# Microcontroller.net
KiCad netlist of a schematic drawn in Altium Designer
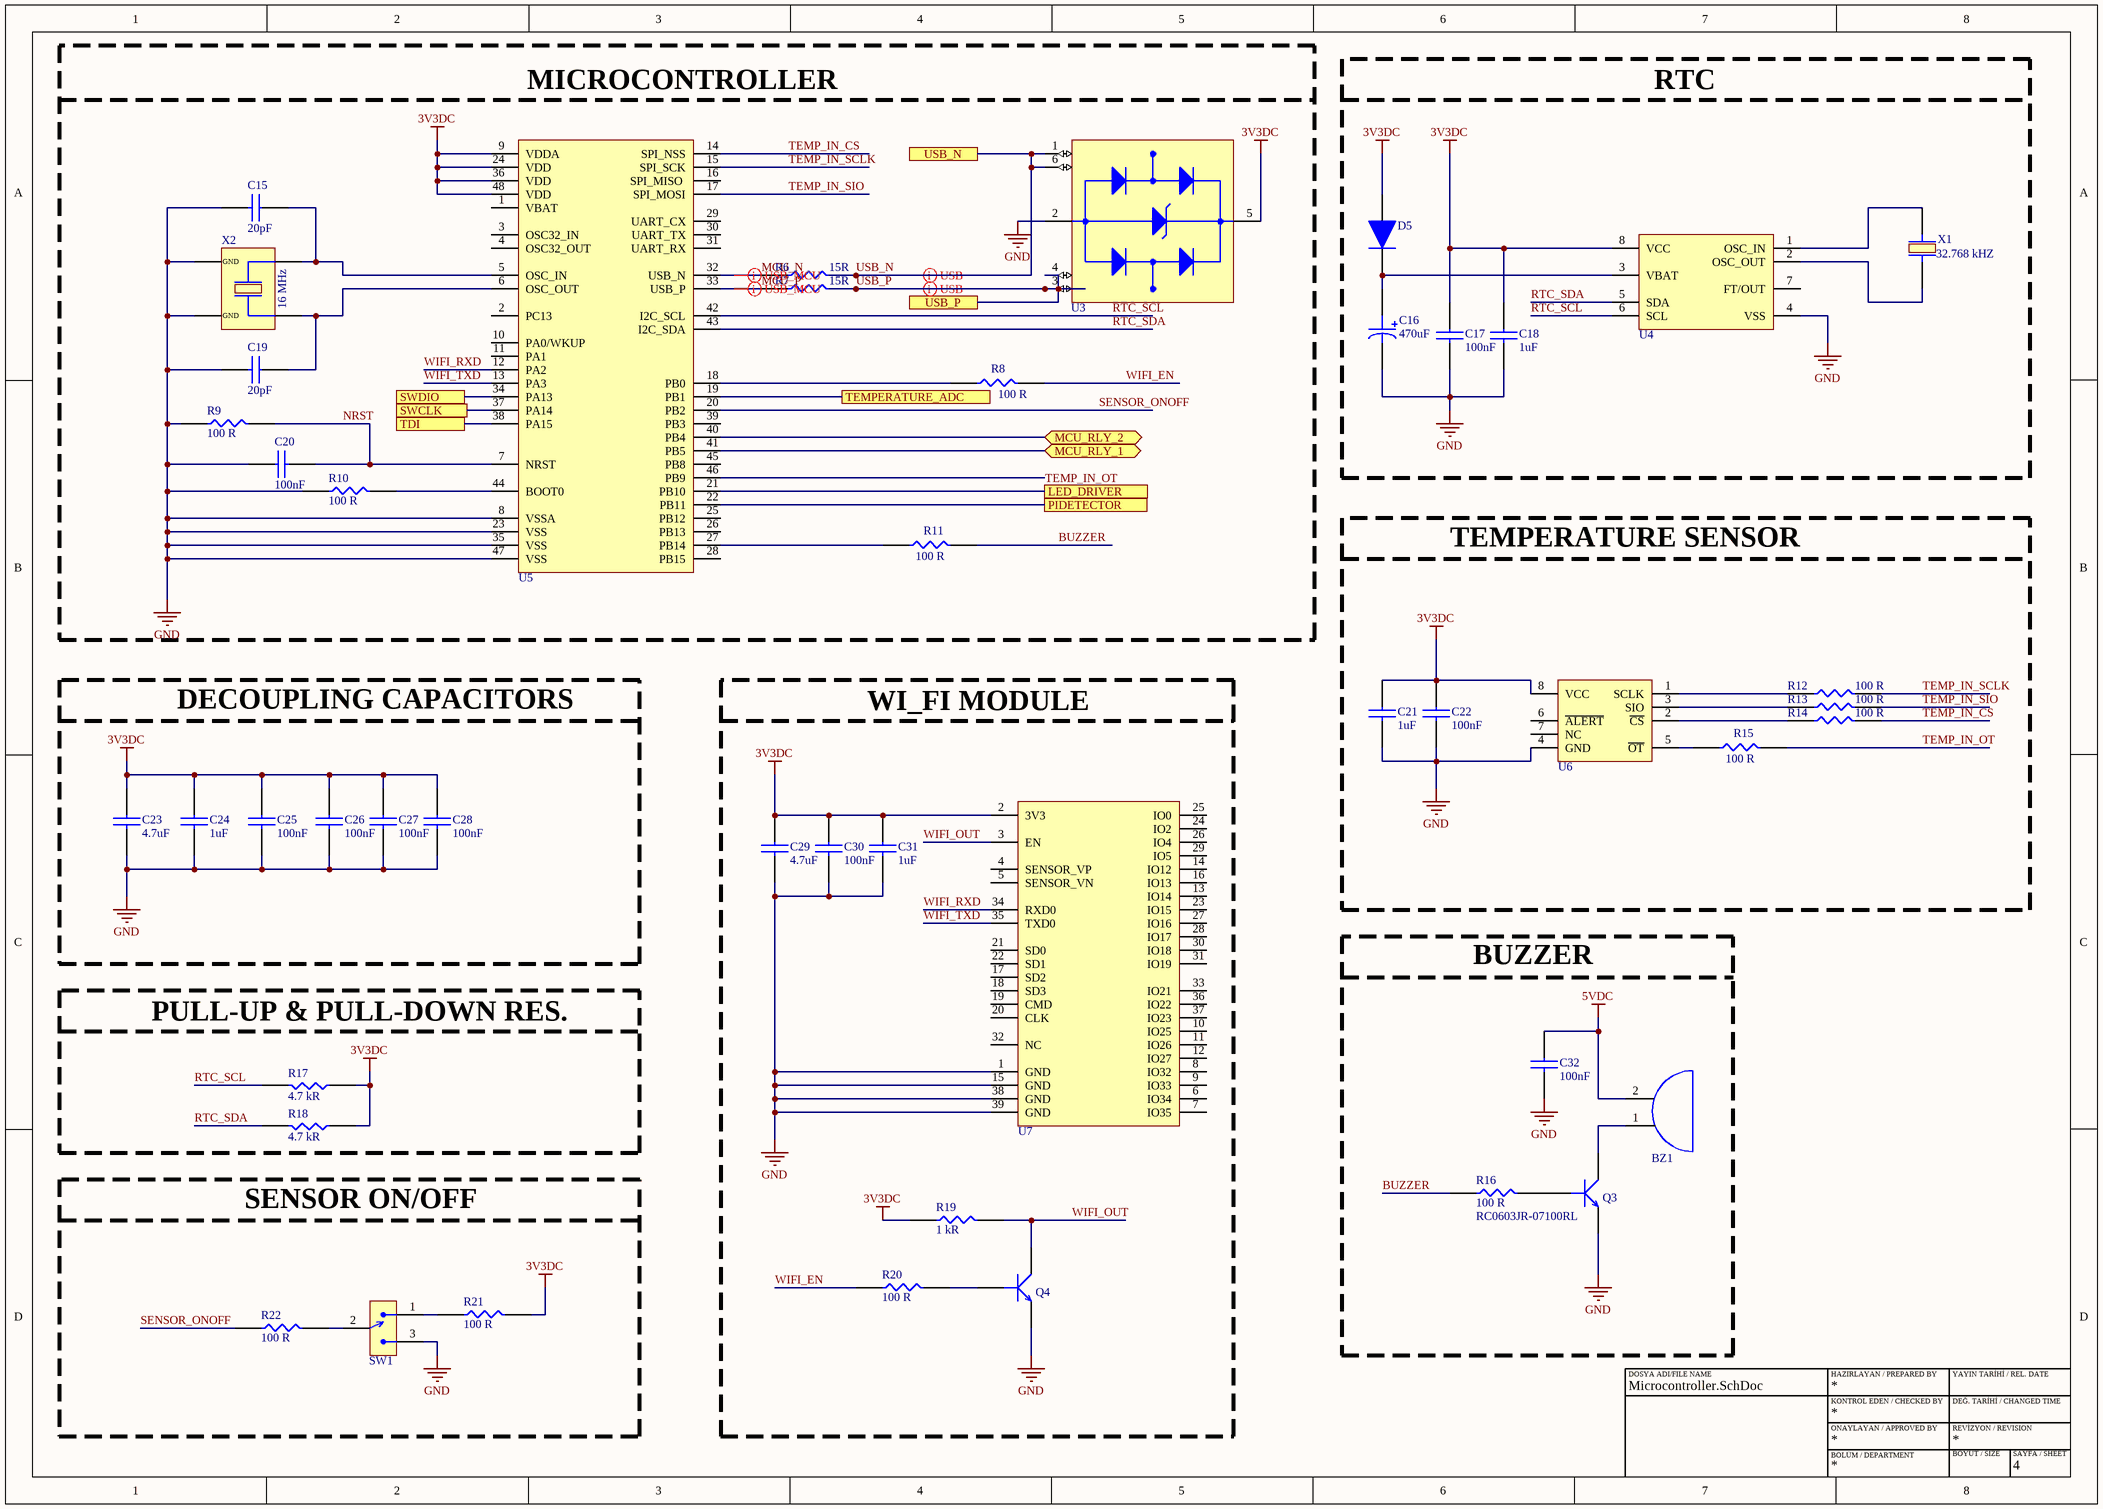
[diagram p0: Microcontroller.SchDoc]

(export (version "E")
  (design (tool "Eeschema 10.0.6"))
  (components
    (comp (ref "BZ1")
      (value "CMI-9605IC-0580T")
      (footprint "CMI-9605IC-0580T")
      (fields
        (field (name "MANUFACTURER") "Same Sky")
        (field (name "MANUFACTURER PART NUMBER") "CMI-9705-0580-SMT-TR")
      )
      (libsource (lib "Integrated_Library1") (part "CMI-9605IC-0580T"))
    )
    (comp (ref "C15")
      (value "20pF")
      (footprint "CAP_0603")
      (description "CAP CER 20pF 5% 0603")
      (fields
        (field (name "MANUFACTURER") "Samsung")
        (field (name "MANUFACTURER PART NUMBER") "CL10C200JB8NNNC")
      )
      (libsource (lib "Integrated_Library1") (part "CAP CER 20pF 0603"))
    )
    (comp (ref "C16")
      (value "470uF")
      (footprint "CAP_RADIAL_D10_P5")
      (description "CAP ALU ELEC 470uF 50V 20%")
      (fields
        (field (name "MANUFACTURER") "KEMET")
        (field (name "MANUFACTURER PART NUMBER") "ESH477M050AH4AA")
        (field (name "DESIGNED BY") "MCP")
      )
      (libsource (lib "Integrated_Library1") (part "CAP ALU ELEC 470uF 50V"))
    )
    (comp (ref "C17")
      (value "100nF")
      (footprint "CAP_0805")
      (description "CAP CER 100nF 10% 0805")
      (fields
        (field (name "MANUFACTURER") "Samsung")
        (field (name "MANUFACTURER PART NUMBER") "CL21B104KBCNNNC")
        (field (name "DESIGNED BY") "MCP")
      )
      (libsource (lib "Integrated_Library1") (part "CAP CER 100nF 0805"))
    )
    (comp (ref "C18")
      (value "1uF")
      (footprint "CAP_0805")
      (description "CAP CER 1uF 10% 0805")
      (fields
        (field (name "MANUFACTURER") "Samsung")
        (field (name "MANUFACTURER PART NUMBER") "CL21B105KBFNNNE")
        (field (name "DESIGNED BY") "MCP")
      )
      (libsource (lib "Integrated_Library1") (part "CAP CER 1uF 0805"))
    )
    (comp (ref "C19")
      (value "20pF")
      (footprint "CAP_0603")
      (description "CAP CER 20pF 5% 0603")
      (fields
        (field (name "MANUFACTURER") "Samsung")
        (field (name "MANUFACTURER PART NUMBER") "CL10C200JB8NNNC")
      )
      (libsource (lib "Integrated_Library1") (part "CAP CER 20pF 0603"))
    )
    (comp (ref "C20")
      (value "100nF")
      (footprint "CAP_0805")
      (description "CAP CER 100nF 10% 0805")
      (fields
        (field (name "MANUFACTURER") "Samsung")
        (field (name "MANUFACTURER PART NUMBER") "CL21B104KBCNNNC")
        (field (name "DESIGNED BY") "MCP")
      )
      (libsource (lib "Integrated_Library1") (part "CAP CER 100nF 0805"))
    )
    (comp (ref "C21")
      (value "1uF")
      (footprint "CAP_0805")
      (description "CAP CER 1uF 10% 0805")
      (fields
        (field (name "MANUFACTURER") "Samsung")
        (field (name "MANUFACTURER PART NUMBER") "CL21B105KBFNNNE")
        (field (name "DESIGNED BY") "MCP")
      )
      (libsource (lib "Integrated_Library1") (part "CAP CER 1uF 0805"))
    )
    (comp (ref "C22")
      (value "100nF")
      (footprint "CAP_0805")
      (description "CAP CER 100nF 10% 0805")
      (fields
        (field (name "MANUFACTURER") "Samsung")
        (field (name "MANUFACTURER PART NUMBER") "CL21B104KBCNNNC")
        (field (name "DESIGNED BY") "MCP")
      )
      (libsource (lib "Integrated_Library1") (part "CAP CER 100nF 0805"))
    )
    (comp (ref "C23")
      (value "4.7uF")
      (footprint "CAP_0805")
      (description "CAP CER 4.7uF 10% 0805")
      (fields
        (field (name "MANUFACTURER") "Samsung")
        (field (name "MANUFACTURER PART NUMBER") "CL21A475KAQNNNE")
        (field (name "DESIGNED BY") "MCP")
      )
      (libsource (lib "Integrated_Library1") (part "CAP CER 4.7uF 0805"))
    )
    (comp (ref "C24")
      (value "1uF")
      (footprint "CAP_0805")
      (description "CAP CER 1uF 10% 0805")
      (fields
        (field (name "MANUFACTURER") "Samsung")
        (field (name "MANUFACTURER PART NUMBER") "CL21B105KBFNNNE")
        (field (name "DESIGNED BY") "MCP")
      )
      (libsource (lib "Integrated_Library1") (part "CAP CER 1uF 0805"))
    )
    (comp (ref "C25")
      (value "100nF")
      (footprint "CAP_0805")
      (description "CAP CER 100nF 10% 0805")
      (fields
        (field (name "MANUFACTURER") "Samsung")
        (field (name "MANUFACTURER PART NUMBER") "CL21B104KBCNNNC")
        (field (name "DESIGNED BY") "MCP")
      )
      (libsource (lib "Integrated_Library1") (part "CAP CER 100nF 0805"))
    )
    (comp (ref "C26")
      (value "100nF")
      (footprint "CAP_0805")
      (description "CAP CER 100nF 10% 0805")
      (fields
        (field (name "MANUFACTURER") "Samsung")
        (field (name "MANUFACTURER PART NUMBER") "CL21B104KBCNNNC")
        (field (name "DESIGNED BY") "MCP")
      )
      (libsource (lib "Integrated_Library1") (part "CAP CER 100nF 0805"))
    )
    (comp (ref "C27")
      (value "100nF")
      (footprint "CAP_0805")
      (description "CAP CER 100nF 10% 0805")
      (fields
        (field (name "MANUFACTURER") "Samsung")
        (field (name "MANUFACTURER PART NUMBER") "CL21B104KBCNNNC")
        (field (name "DESIGNED BY") "MCP")
      )
      (libsource (lib "Integrated_Library1") (part "CAP CER 100nF 0805"))
    )
    (comp (ref "C28")
      (value "100nF")
      (footprint "CAP_0805")
      (description "CAP CER 100nF 10% 0805")
      (fields
        (field (name "MANUFACTURER") "Samsung")
        (field (name "MANUFACTURER PART NUMBER") "CL21B104KBCNNNC")
        (field (name "DESIGNED BY") "MCP")
      )
      (libsource (lib "Integrated_Library1") (part "CAP CER 100nF 0805"))
    )
    (comp (ref "C29")
      (value "4.7uF")
      (footprint "CAP_0805")
      (description "CAP CER 4.7uF 10% 0805")
      (fields
        (field (name "MANUFACTURER") "Samsung")
        (field (name "MANUFACTURER PART NUMBER") "CL21A475KAQNNNE")
        (field (name "DESIGNED BY") "MCP")
      )
      (libsource (lib "Integrated_Library1") (part "CAP CER 4.7uF 0805"))
    )
    (comp (ref "C30")
      (value "100nF")
      (footprint "CAP_0805")
      (description "CAP CER 100nF 10% 0805")
      (fields
        (field (name "MANUFACTURER") "Samsung")
        (field (name "MANUFACTURER PART NUMBER") "CL21B104KBCNNNC")
        (field (name "DESIGNED BY") "MCP")
      )
      (libsource (lib "Integrated_Library1") (part "CAP CER 100nF 0805"))
    )
    (comp (ref "C31")
      (value "1uF")
      (footprint "CAP_0805")
      (description "CAP CER 1uF 10% 0805")
      (fields
        (field (name "MANUFACTURER") "Samsung")
        (field (name "MANUFACTURER PART NUMBER") "CL21B105KBFNNNE")
        (field (name "DESIGNED BY") "MCP")
      )
      (libsource (lib "Integrated_Library1") (part "CAP CER 1uF 0805"))
    )
    (comp (ref "C32")
      (value "100nF")
      (footprint "CAP_0805")
      (description "CAP CER 100nF 10% 0805")
      (fields
        (field (name "MANUFACTURER") "Samsung")
        (field (name "MANUFACTURER PART NUMBER") "CL21B104KBCNNNC")
        (field (name "DESIGNED BY") "MCP")
      )
      (libsource (lib "Integrated_Library1") (part "CAP CER 100nF 0805"))
    )
    (comp (ref "D5")
      (value "1N4148WS")
      (footprint "SOD323F")
      (description "Diode,150mA, 75V V")
      (fields (field (name "MANUFACTURER") "onsemi") (field (name "DESIGNED BY") "MCP"))
      (libsource (lib "Integrated_Library1") (part "1N4148WS"))
    )
    (comp (ref "Q3")
      (value "MMBT3904.7.F")
      (footprint "SOT-23F")
      (description "Small Signal Bipolar Transistor, 0.2A I(C), 40V V(BR)CEO, 1-Element, NPN, Silicon")
      (fields
        (field (name "MANUFACTURER") "Diodes Zetex")
        (field (name "MANUFACTURER PART NUMBER") "MMBT3904-7-F")
        (field (name "DESIGNED BY") "MCP")
      )
      (libsource (lib "Integrated_Library1") (part "MMBT3904.7.F"))
    )
    (comp (ref "Q4")
      (value "MMBT3904.7.F")
      (footprint "SOT-23F")
      (description "Small Signal Bipolar Transistor, 0.2A I(C), 40V V(BR)CEO, 1-Element, NPN, Silicon")
      (fields
        (field (name "MANUFACTURER") "Diodes Zetex")
        (field (name "MANUFACTURER PART NUMBER") "MMBT3904-7-F")
        (field (name "DESIGNED BY") "MCP")
      )
      (libsource (lib "Integrated_Library1") (part "MMBT3904.7.F"))
    )
    (comp (ref "R6")
      (value "15R")
      (footprint "RES_0603")
      (fields
        (field (name "MANUFACTURER") "Yageo")
        (field (name "MANUFACTURER PART NUMBER") "RC0603JR-0715RL")
        (field (name "TOLERANCE") "5%")
      )
      (libsource (lib "Integrated_Library1") (part "RES 15 OHM 0603"))
    )
    (comp (ref "R7")
      (value "15R")
      (footprint "RES_0603")
      (fields
        (field (name "MANUFACTURER") "Yageo")
        (field (name "MANUFACTURER PART NUMBER") "RC0603JR-0715RL")
        (field (name "TOLERANCE") "5%")
      )
      (libsource (lib "Integrated_Library1") (part "RES 15 OHM 0603"))
    )
    (comp (ref "R8")
      (value "100 R")
      (footprint "RES_0603")
      (fields
        (field (name "MANUFACTURER") "Yageo")
        (field (name "MANUFACTURER PART NUMBER") "RC0603JR-07100RL")
        (field (name "TOLERANCE") "5%")
      )
      (libsource (lib "Integrated_Library1") (part "RES 100 OHM 0603"))
    )
    (comp (ref "R9")
      (value "100 R")
      (footprint "RES_0603")
      (fields
        (field (name "MANUFACTURER") "Yageo")
        (field (name "MANUFACTURER PART NUMBER") "RC0603JR-07100RL")
        (field (name "TOLERANCE") "5%")
      )
      (libsource (lib "Integrated_Library1") (part "RES 100 OHM 0603"))
    )
    (comp (ref "R10")
      (value "100 R")
      (footprint "RES_0603")
      (fields
        (field (name "MANUFACTURER") "Yageo")
        (field (name "MANUFACTURER PART NUMBER") "RC0603JR-07100RL")
        (field (name "TOLERANCE") "5%")
      )
      (libsource (lib "Integrated_Library1") (part "RES 100 OHM 0603"))
    )
    (comp (ref "R11")
      (value "100 R")
      (footprint "RES_0603")
      (fields
        (field (name "MANUFACTURER") "Yageo")
        (field (name "MANUFACTURER PART NUMBER") "RC0603JR-07100RL")
        (field (name "TOLERANCE") "5%")
      )
      (libsource (lib "Integrated_Library1") (part "RES 100 OHM 0603"))
    )
    (comp (ref "R12")
      (value "100 R")
      (footprint "RES_0603")
      (fields
        (field (name "MANUFACTURER") "Yageo")
        (field (name "MANUFACTURER PART NUMBER") "RC0603JR-07100RL")
        (field (name "TOLERANCE") "5%")
      )
      (libsource (lib "Integrated_Library1") (part "RES 100 OHM 0603"))
    )
    (comp (ref "R13")
      (value "100 R")
      (footprint "RES_0603")
      (fields
        (field (name "MANUFACTURER") "Yageo")
        (field (name "MANUFACTURER PART NUMBER") "RC0603JR-07100RL")
        (field (name "TOLERANCE") "5%")
      )
      (libsource (lib "Integrated_Library1") (part "RES 100 OHM 0603"))
    )
    (comp (ref "R14")
      (value "100 R")
      (footprint "RES_0603")
      (fields
        (field (name "MANUFACTURER") "Yageo")
        (field (name "MANUFACTURER PART NUMBER") "RC0603JR-07100RL")
        (field (name "TOLERANCE") "5%")
      )
      (libsource (lib "Integrated_Library1") (part "RES 100 OHM 0603"))
    )
    (comp (ref "R15")
      (value "100 R")
      (footprint "RES_0603")
      (fields
        (field (name "MANUFACTURER") "Yageo")
        (field (name "MANUFACTURER PART NUMBER") "RC0603JR-07100RL")
        (field (name "TOLERANCE") "5%")
      )
      (libsource (lib "Integrated_Library1") (part "RES 100 OHM 0603"))
    )
    (comp (ref "R16")
      (value "RC0603JR-07100RL")
      (footprint "RES_0603")
      (fields
        (field (name "MANUFACTURER") "Yageo")
        (field (name "TOLERANCE") "5%")
        (field (name "POWER") "100mW")
        (field (name "ALTIUM_VALUE") "100 R")
      )
      (libsource (lib "Integrated_Library1") (part "RES 100 OHM 0603"))
    )
    (comp (ref "R17")
      (value "4.7 kR")
      (footprint "RES_0603")
      (fields
        (field (name "MANUFACTURER") "Yageo")
        (field (name "MANUFACTURER PART NUMBER") "RC0603JR-074K7L")
        (field (name "TOLERANCE") "5%")
      )
      (libsource (lib "Integrated_Library1") (part "RES 4K7 OHM 0603"))
    )
    (comp (ref "R18")
      (value "4.7 kR")
      (footprint "RES_0603")
      (fields
        (field (name "MANUFACTURER") "Yageo")
        (field (name "MANUFACTURER PART NUMBER") "RC0603JR-074K7L")
        (field (name "TOLERANCE") "5%")
      )
      (libsource (lib "Integrated_Library1") (part "RES 4K7 OHM 0603"))
    )
    (comp (ref "R19")
      (value "1 kR")
      (footprint "RES_0603")
      (fields
        (field (name "MANUFACTURER") "Stackpole Electronics")
        (field (name "MANUFACTURER PART NUMBER") "RMCF0603FT1K00")
        (field (name "TOLERANCE") "1%")
      )
      (libsource (lib "Integrated_Library1") (part "RES 1K OHM 0603"))
    )
    (comp (ref "R20")
      (value "100 R")
      (footprint "RES_0603")
      (fields
        (field (name "MANUFACTURER") "Yageo")
        (field (name "MANUFACTURER PART NUMBER") "RC0603JR-07100RL")
        (field (name "TOLERANCE") "5%")
      )
      (libsource (lib "Integrated_Library1") (part "RES 100 OHM 0603"))
    )
    (comp (ref "R21")
      (value "100 R")
      (footprint "RES_0603")
      (fields
        (field (name "MANUFACTURER") "Yageo")
        (field (name "MANUFACTURER PART NUMBER") "RC0603JR-07100RL")
        (field (name "TOLERANCE") "5%")
      )
      (libsource (lib "Integrated_Library1") (part "RES 100 OHM 0603"))
    )
    (comp (ref "R22")
      (value "100 R")
      (footprint "RES_0603")
      (fields
        (field (name "MANUFACTURER") "Yageo")
        (field (name "MANUFACTURER PART NUMBER") "RC0603JR-07100RL")
        (field (name "TOLERANCE") "5%")
      )
      (libsource (lib "Integrated_Library1") (part "RES 100 OHM 0603"))
    )
    (comp (ref "SW1")
      (value "EG1215AA")
      (footprint "EG1215AA")
      (description "Slide Switch")
      (fields (field (name "MANUFACTURER") "E-Switch"))
      (libsource (lib "Integrated_Library1") (part "EG1215AA"))
    )
    (comp (ref "U3")
      (value "USBLC6-2SC6")
      (footprint "SOT23-6L")
      (description "Trans Voltage Suppressor Diode, 5V V(RWM), Unidirectional, 1 Element, Silicon")
      (fields (field (name "MANUFACTURER") "STMicroelectronics"))
      (libsource (lib "Integrated_Library1") (part "USB PROTECTION"))
    )
    (comp (ref "U4")
      (value "M41T00M6F")
      (footprint "SOIC-8")
      (description "Real Time Clock, Volatile, CMOS, PDSO8")
      (fields (field (name "MANUFACTURER") "STMicroelectronics") (field (name "DESIGNED BY") "MCP"))
      (libsource (lib "Integrated_Library1") (part "M41T00M6F"))
    )
    (comp (ref "U5")
      (value "STM32F103C6T6A")
      (footprint "LQFP-48")
      (description "MCU 32-bit STM32F ARM Cortex M3 RISC 32KB Flash 2.5V/3.3V 48-Pin LQFP Tray")
      (fields (field (name "MANUFACTURER") "STMicroelectronics") (field (name "DESIGNED BY") "MCP"))
      (libsource (lib "Integrated_Library1") (part "STM32F103C6T6A"))
    )
    (comp (ref "U6")
      (value "MAX6662MSA+")
      (footprint "SOIC-8")
      (description "Serial Switch/Digital Sensor, 12 Bit(s), 2.50Cel, BICMOS, Rectangular, 8 Pin, Surface Mount")
      (fields (field (name "MANUFACTURER") "Maxim") (field (name "DESIGNED BY") "MCP"))
      (libsource (lib "Integrated_Library1") (part "MAX6662MSA+"))
    )
    (comp (ref "U7")
      (value "ESP32-WROOM-32E")
      (footprint "ESP32-32E")
      (description "ESP32-WROOM-32E 4MB Flash")
      (fields
        (field (name "MANUFACTURER") "Espressif Systems")
        (field (name "MANUFACTURER PART NUMBER") "ESP32-DEVKITC-32E")
        (field (name "DESIGNED BY") "MCP")
      )
      (libsource (lib "Integrated_Library1") (part "ESP32-WROOM-32E"))
    )
    (comp (ref "X1")
      (value "ABS05-32.768KHZ-T")
      (footprint "ABS05")
      (description "Parallel - Fundamental Quartz Crystal, 0.032768MHz Nom")
      (fields (field (name "MANUFACTURER") "Abracon") (field (name "OPERATING FREQUENCY-NOM") "32.768 kHZ"))
      (libsource (lib "Integrated_Library1") (part "CRYSTAL 32768kHZ"))
    )
    (comp (ref "X2")
      (value "ECS-160-20-30B-TR")
      (footprint "ECS")
      (description "Parallel - Fundamental Quartz Crystal, 16MHz Nom")
      (fields
        (field (name "MANUFACTURER") "ECS International")
        (field (name "OPERATING FREQUENCY-NOM") "16 MHz")
      )
      (libsource (lib "Integrated_Library1") (part "CRYSTAL 16MHz"))
    )
  )
  (nets
    (net (code "1") (name "/BUZZER") (class "Default")
      (node (ref "R11") (pin "2") (pinfunction "2_2") (pintype "passive"))
      (node (ref "R16") (pin "1") (pinfunction "1_1") (pintype "passive"))
    )
    (net (code "2") (name "/LED_DRIVER") (class "Default")
      (node (ref "U5") (pin "21") (pinfunction "PB10_21") (pintype "passive"))
    )
    (net (code "3") (name "/MCU_N") (class "Default")
      (node (ref "R6") (pin "1") (pinfunction "1_1") (pintype "passive"))
      (node (ref "U5") (pin "32") (pinfunction "USB_N_32") (pintype "passive"))
    )
    (net (code "4") (name "/MCU_P") (class "Default")
      (node (ref "R7") (pin "1") (pinfunction "1_1") (pintype "passive"))
      (node (ref "U5") (pin "33") (pinfunction "USB_P_33") (pintype "passive"))
    )
    (net (code "5") (name "/MCU_RLY_1") (class "Default")
      (node (ref "U5") (pin "41") (pinfunction "PB5_41") (pintype "passive"))
    )
    (net (code "6") (name "/MCU_RLY_2") (class "Default")
      (node (ref "U5") (pin "40") (pinfunction "PB4_40") (pintype "passive"))
    )
    (net (code "7") (name "/NRST") (class "Default")
      (node (ref "C20") (pin "1") (pinfunction "1_1") (pintype "passive"))
      (node (ref "R9") (pin "2") (pinfunction "2_2") (pintype "passive"))
      (node (ref "U5") (pin "7") (pinfunction "NRST_7") (pintype "passive"))
    )
    (net (code "8") (name "/PIDETECTOR") (class "Default")
      (node (ref "U5") (pin "22") (pinfunction "PB11_22") (pintype "passive"))
    )
    (net (code "9") (name "/RTC_SCL") (class "Default")
      (node (ref "R17") (pin "1") (pinfunction "1_1") (pintype "passive"))
      (node (ref "U4") (pin "6") (pinfunction "SCL_6") (pintype "passive"))
      (node (ref "U5") (pin "42") (pinfunction "I2C_SCL_42") (pintype "passive"))
    )
    (net (code "10") (name "/RTC_SDA") (class "Default")
      (node (ref "R18") (pin "1") (pinfunction "1_1") (pintype "passive"))
      (node (ref "U4") (pin "5") (pinfunction "SDA_5") (pintype "passive"))
      (node (ref "U5") (pin "43") (pinfunction "I2C_SDA_43") (pintype "passive"))
    )
    (net (code "11") (name "/SENSOR_ONOFF") (class "Default")
      (node (ref "R22") (pin "1") (pinfunction "1_1") (pintype "passive"))
      (node (ref "U5") (pin "20") (pinfunction "PB2_20") (pintype "passive"))
    )
    (net (code "12") (name "/SWCLK") (class "Default")
      (node (ref "U5") (pin "37") (pinfunction "PA14_37") (pintype "passive"))
    )
    (net (code "13") (name "/SWDIO") (class "Default")
      (node (ref "U5") (pin "34") (pinfunction "PA13_34") (pintype "passive"))
    )
    (net (code "14") (name "/TDI") (class "Default")
      (node (ref "U5") (pin "38") (pinfunction "PA15_38") (pintype "passive"))
    )
    (net (code "15") (name "/TEMPERATURE_ADC") (class "Default")
      (node (ref "U5") (pin "19") (pinfunction "PB1_19") (pintype "passive"))
    )
    (net (code "16") (name "/TEMP_IN_CS") (class "Default")
      (node (ref "R14") (pin "2") (pinfunction "2_2") (pintype "passive"))
      (node (ref "U5") (pin "14") (pinfunction "SPI_NSS_14") (pintype "passive"))
    )
    (net (code "17") (name "/TEMP_IN_OT") (class "Default")
      (node (ref "R15") (pin "2") (pinfunction "2_2") (pintype "passive"))
      (node (ref "U5") (pin "46") (pinfunction "PB9_46") (pintype "passive"))
    )
    (net (code "18") (name "/TEMP_IN_SCLK") (class "Default")
      (node (ref "R12") (pin "2") (pinfunction "2_2") (pintype "passive"))
      (node (ref "U5") (pin "15") (pinfunction "SPI_SCK_15") (pintype "passive"))
    )
    (net (code "19") (name "/TEMP_IN_SIO") (class "Default")
      (node (ref "R13") (pin "2") (pinfunction "2_2") (pintype "passive"))
      (node (ref "U5") (pin "17") (pinfunction "SPI_MOSI_17") (pintype "passive"))
    )
    (net (code "20") (name "/USB_N") (class "Default")
      (node (ref "R6") (pin "2") (pinfunction "2_2") (pintype "passive"))
      (node (ref "U3") (pin "1") (pinfunction "I/O1_IN_1") (pintype "bidirectional"))
      (node (ref "U3") (pin "6") (pinfunction "I/O1_OUT_6") (pintype "bidirectional"))
    )
    (net (code "21") (name "/USB_P") (class "Default")
      (node (ref "R7") (pin "2") (pinfunction "2_2") (pintype "passive"))
      (node (ref "U3") (pin "3") (pinfunction "I/O2_IN_3") (pintype "bidirectional"))
      (node (ref "U3") (pin "4") (pinfunction "I/O2_OUT_4") (pintype "bidirectional"))
    )
    (net (code "22") (name "/WIFI_EN") (class "Default")
      (node (ref "R20") (pin "1") (pinfunction "1_1") (pintype "passive"))
      (node (ref "R8") (pin "2") (pinfunction "2_2") (pintype "passive"))
    )
    (net (code "23") (name "/WIFI_OUT") (class "Default")
      (node (ref "Q4") (pin "3") (pinfunction "C_3") (pintype "passive"))
      (node (ref "R19") (pin "2") (pinfunction "2_2") (pintype "passive"))
      (node (ref "U7") (pin "3") (pinfunction "EN_3") (pintype "passive"))
    )
    (net (code "24") (name "/WIFI_RXD") (class "Default")
      (node (ref "U5") (pin "12") (pinfunction "PA2_12") (pintype "passive"))
      (node (ref "U7") (pin "34") (pinfunction "RXD0_34") (pintype "passive"))
    )
    (net (code "25") (name "/WIFI_TXD") (class "Default")
      (node (ref "U5") (pin "13") (pinfunction "PA3_13") (pintype "passive"))
      (node (ref "U7") (pin "35") (pinfunction "TXD0_35") (pintype "passive"))
    )
    (net (code "26") (name "3V3DC") (class "Default")
      (node (ref "C17") (pin "2") (pinfunction "2_2") (pintype "passive"))
      (node (ref "C18") (pin "2") (pinfunction "2_2") (pintype "passive"))
      (node (ref "C21") (pin "2") (pinfunction "2_2") (pintype "passive"))
      (node (ref "C22") (pin "2") (pinfunction "2_2") (pintype "passive"))
      (node (ref "C23") (pin "2") (pinfunction "2_2") (pintype "passive"))
      (node (ref "C24") (pin "2") (pinfunction "2_2") (pintype "passive"))
      (node (ref "C25") (pin "2") (pinfunction "2_2") (pintype "passive"))
      (node (ref "C26") (pin "2") (pinfunction "2_2") (pintype "passive"))
      (node (ref "C27") (pin "2") (pinfunction "2_2") (pintype "passive"))
      (node (ref "C28") (pin "2") (pinfunction "2_2") (pintype "passive"))
      (node (ref "C29") (pin "2") (pinfunction "2_2") (pintype "passive"))
      (node (ref "C30") (pin "2") (pinfunction "2_2") (pintype "passive"))
      (node (ref "C31") (pin "2") (pinfunction "2_2") (pintype "passive"))
      (node (ref "D5") (pin "2") (pinfunction "2_2") (pintype "passive"))
      (node (ref "R17") (pin "2") (pinfunction "2_2") (pintype "passive"))
      (node (ref "R18") (pin "2") (pinfunction "2_2") (pintype "passive"))
      (node (ref "R19") (pin "1") (pinfunction "1_1") (pintype "passive"))
      (node (ref "R21") (pin "2") (pinfunction "2_2") (pintype "passive"))
      (node (ref "U3") (pin "5") (pinfunction "VBUS_5") (pintype "power_in"))
      (node (ref "U4") (pin "8") (pinfunction "VCC_8") (pintype "passive"))
      (node (ref "U5") (pin "24") (pinfunction "VDD_24") (pintype "passive"))
      (node (ref "U5") (pin "36") (pinfunction "VDD_36") (pintype "passive"))
      (node (ref "U5") (pin "48") (pinfunction "VDD_48") (pintype "passive"))
      (node (ref "U5") (pin "9") (pinfunction "VDDA_9") (pintype "passive"))
      (node (ref "U6") (pin "8") (pinfunction "VCC_8") (pintype "passive"))
      (node (ref "U7") (pin "2") (pinfunction "3V3_2") (pintype "passive"))
    )
    (net (code "27") (name "5VDC") (class "Default")
      (node (ref "BZ1") (pin "2") (pinfunction "2_2") (pintype "passive"))
      (node (ref "C32") (pin "2") (pinfunction "2_2") (pintype "passive"))
    )
    (net (code "28") (name "GND") (class "Default")
      (node (ref "C15") (pin "1") (pinfunction "1_1") (pintype "passive"))
      (node (ref "C16") (pin "2") (pinfunction "2_2") (pintype "passive"))
      (node (ref "C17") (pin "1") (pinfunction "1_1") (pintype "passive"))
      (node (ref "C18") (pin "1") (pinfunction "1_1") (pintype "passive"))
      (node (ref "C19") (pin "1") (pinfunction "1_1") (pintype "passive"))
      (node (ref "C20") (pin "2") (pinfunction "2_2") (pintype "passive"))
      (node (ref "C21") (pin "1") (pinfunction "1_1") (pintype "passive"))
      (node (ref "C22") (pin "1") (pinfunction "1_1") (pintype "passive"))
      (node (ref "C23") (pin "1") (pinfunction "1_1") (pintype "passive"))
      (node (ref "C24") (pin "1") (pinfunction "1_1") (pintype "passive"))
      (node (ref "C25") (pin "1") (pinfunction "1_1") (pintype "passive"))
      (node (ref "C26") (pin "1") (pinfunction "1_1") (pintype "passive"))
      (node (ref "C27") (pin "1") (pinfunction "1_1") (pintype "passive"))
      (node (ref "C28") (pin "1") (pinfunction "1_1") (pintype "passive"))
      (node (ref "C29") (pin "1") (pinfunction "1_1") (pintype "passive"))
      (node (ref "C30") (pin "1") (pinfunction "1_1") (pintype "passive"))
      (node (ref "C31") (pin "1") (pinfunction "1_1") (pintype "passive"))
      (node (ref "C32") (pin "1") (pinfunction "1_1") (pintype "passive"))
      (node (ref "Q3") (pin "2") (pinfunction "E_2") (pintype "passive"))
      (node (ref "Q4") (pin "2") (pinfunction "E_2") (pintype "passive"))
      (node (ref "R10") (pin "1") (pinfunction "1_1") (pintype "passive"))
      (node (ref "R9") (pin "1") (pinfunction "1_1") (pintype "passive"))
      (node (ref "SW1") (pin "3") (pinfunction "3_3") (pintype "passive"))
      (node (ref "U3") (pin "2") (pinfunction "GND_2") (pintype "power_in"))
      (node (ref "U4") (pin "4") (pinfunction "VSS_4") (pintype "passive"))
      (node (ref "U5") (pin "23") (pinfunction "VSS_23") (pintype "passive"))
      (node (ref "U5") (pin "35") (pinfunction "VSS_35") (pintype "passive"))
      (node (ref "U5") (pin "47") (pinfunction "VSS_47") (pintype "passive"))
      (node (ref "U5") (pin "8") (pinfunction "VSSA_8") (pintype "passive"))
      (node (ref "U6") (pin "4") (pinfunction "GND_4") (pintype "passive"))
      (node (ref "U7") (pin "1") (pinfunction "GND_1") (pintype "passive"))
      (node (ref "U7") (pin "15") (pinfunction "GND_15") (pintype "passive"))
      (node (ref "U7") (pin "38") (pinfunction "GND_38") (pintype "passive"))
      (node (ref "U7") (pin "39") (pinfunction "GND_39") (pintype "passive"))
      (node (ref "X2") (pin "2") (pinfunction "GND_2") (pintype "passive"))
      (node (ref "X2") (pin "4") (pinfunction "GND_4") (pintype "passive"))
    )
    (net (code "29") (name "Net-(Q3-B)") (class "Default")
      (node (ref "Q3") (pin "1") (pinfunction "B_1") (pintype "passive"))
      (node (ref "R16") (pin "2") (pinfunction "2_2") (pintype "passive"))
    )
    (net (code "30") (name "Net-(Q3-C)") (class "Default")
      (node (ref "BZ1") (pin "1") (pinfunction "1_1") (pintype "passive"))
      (node (ref "Q3") (pin "3") (pinfunction "C_3") (pintype "passive"))
    )
    (net (code "31") (name "Net-(Q4-B)") (class "Default")
      (node (ref "Q4") (pin "1") (pinfunction "B_1") (pintype "passive"))
      (node (ref "R20") (pin "2") (pinfunction "2_2") (pintype "passive"))
    )
    (net (code "32") (name "Net-(R21-Pad1)") (class "Default")
      (node (ref "R21") (pin "1") (pinfunction "1_1") (pintype "passive"))
      (node (ref "SW1") (pin "1") (pinfunction "1_1") (pintype "passive"))
    )
    (net (code "33") (name "Net-(R22-Pad2)") (class "Default")
      (node (ref "R22") (pin "2") (pinfunction "2_2") (pintype "passive"))
      (node (ref "SW1") (pin "2") (pinfunction "2_2") (pintype "passive"))
    )
    (net (code "34") (name "Net-(U4-OSC_IN)") (class "Default")
      (node (ref "U4") (pin "1") (pinfunction "OSC_IN_1") (pintype "passive"))
      (node (ref "X1") (pin "2") (pinfunction "2_2") (pintype "passive"))
    )
    (net (code "35") (name "Net-(U4-OSC_OUT)") (class "Default")
      (node (ref "U4") (pin "2") (pinfunction "OSC_OUT_2") (pintype "passive"))
      (node (ref "X1") (pin "1") (pinfunction "1_1") (pintype "passive"))
    )
    (net (code "36") (name "Net-(U4-VBAT)") (class "Default")
      (node (ref "C16") (pin "1") (pinfunction "1_1") (pintype "passive"))
      (node (ref "D5") (pin "1") (pinfunction "1_1") (pintype "passive"))
      (node (ref "U4") (pin "3") (pinfunction "VBAT_3") (pintype "passive"))
    )
    (net (code "37") (name "Net-(U5-BOOT0)") (class "Default")
      (node (ref "R10") (pin "2") (pinfunction "2_2") (pintype "passive"))
      (node (ref "U5") (pin "44") (pinfunction "BOOT0_44") (pintype "passive"))
    )
    (net (code "38") (name "Net-(U5-OSC_IN)") (class "Default")
      (node (ref "C15") (pin "2") (pinfunction "2_2") (pintype "passive"))
      (node (ref "U5") (pin "5") (pinfunction "OSC_IN_5") (pintype "passive"))
      (node (ref "X2") (pin "3") (pinfunction "3_3") (pintype "passive"))
    )
    (net (code "39") (name "Net-(U5-OSC_OUT)") (class "Default")
      (node (ref "C19") (pin "2") (pinfunction "2_2") (pintype "passive"))
      (node (ref "U5") (pin "6") (pinfunction "OSC_OUT_6") (pintype "passive"))
      (node (ref "X2") (pin "1") (pinfunction "1_1") (pintype "passive"))
    )
    (net (code "40") (name "Net-(U5-PB0)") (class "Default")
      (node (ref "R8") (pin "1") (pinfunction "1_1") (pintype "passive"))
      (node (ref "U5") (pin "18") (pinfunction "PB0_18") (pintype "passive"))
    )
    (net (code "41") (name "Net-(U5-PB14)") (class "Default")
      (node (ref "R11") (pin "1") (pinfunction "1_1") (pintype "passive"))
      (node (ref "U5") (pin "27") (pinfunction "PB14_27") (pintype "passive"))
    )
    (net (code "42") (name "Net-(U6-SCLK)") (class "Default")
      (node (ref "R12") (pin "1") (pinfunction "1_1") (pintype "passive"))
      (node (ref "U6") (pin "1") (pinfunction "SCLK_1") (pintype "passive"))
    )
    (net (code "43") (name "Net-(U6-SIO)") (class "Default")
      (node (ref "R13") (pin "1") (pinfunction "1_1") (pintype "passive"))
      (node (ref "U6") (pin "3") (pinfunction "SIO_3") (pintype "passive"))
    )
    (net (code "44") (name "Net-(U6-~{CS})") (class "Default")
      (node (ref "R14") (pin "1") (pinfunction "1_1") (pintype "passive"))
      (node (ref "U6") (pin "2") (pinfunction "~{CS}_2") (pintype "passive"))
    )
    (net (code "45") (name "Net-(U6-~{OT})") (class "Default")
      (node (ref "R15") (pin "1") (pinfunction "1_1") (pintype "passive"))
      (node (ref "U6") (pin "5") (pinfunction "~{OT}_5") (pintype "passive"))
    )
    (net (code "46") (name "unconnected-(U4-FT{slash}OUT-Pad7)") (class "Default")
      (node (ref "U4") (pin "7") (pinfunction "FT/OUT_7") (pintype "passive"))
    )
    (net (code "47") (name "unconnected-(U5-OSC32_IN-Pad3)") (class "Default")
      (node (ref "U5") (pin "3") (pinfunction "OSC32_IN_3") (pintype "passive"))
    )
    (net (code "48") (name "unconnected-(U5-OSC32_OUT-Pad4)") (class "Default")
      (node (ref "U5") (pin "4") (pinfunction "OSC32_OUT_4") (pintype "passive"))
    )
    (net (code "49") (name "unconnected-(U5-PA0{slash}WKUP-Pad10)") (class "Default")
      (node (ref "U5") (pin "10") (pinfunction "PA0/WKUP_10") (pintype "passive"))
    )
    (net (code "50") (name "unconnected-(U5-PA1-Pad11)") (class "Default")
      (node (ref "U5") (pin "11") (pinfunction "PA1_11") (pintype "passive"))
    )
    (net (code "51") (name "unconnected-(U5-PB3-Pad39)") (class "Default")
      (node (ref "U5") (pin "39") (pinfunction "PB3_39") (pintype "passive"))
    )
    (net (code "52") (name "unconnected-(U5-PB8-Pad45)") (class "Default")
      (node (ref "U5") (pin "45") (pinfunction "PB8_45") (pintype "passive"))
    )
    (net (code "53") (name "unconnected-(U5-PB12-Pad25)") (class "Default")
      (node (ref "U5") (pin "25") (pinfunction "PB12_25") (pintype "passive"))
    )
    (net (code "54") (name "unconnected-(U5-PB13-Pad26)") (class "Default")
      (node (ref "U5") (pin "26") (pinfunction "PB13_26") (pintype "passive"))
    )
    (net (code "55") (name "unconnected-(U5-PB15-Pad28)") (class "Default")
      (node (ref "U5") (pin "28") (pinfunction "PB15_28") (pintype "passive"))
    )
    (net (code "56") (name "unconnected-(U5-PC13-Pad2)") (class "Default")
      (node (ref "U5") (pin "2") (pinfunction "PC13_2") (pintype "passive"))
    )
    (net (code "57") (name "unconnected-(U5-SPI_MISO-Pad16)") (class "Default")
      (node (ref "U5") (pin "16") (pinfunction "SPI_MISO_16") (pintype "passive"))
    )
    (net (code "58") (name "unconnected-(U5-UART_CX-Pad29)") (class "Default")
      (node (ref "U5") (pin "29") (pinfunction "UART_CX_29") (pintype "passive"))
    )
    (net (code "59") (name "unconnected-(U5-UART_RX-Pad31)") (class "Default")
      (node (ref "U5") (pin "31") (pinfunction "UART_RX_31") (pintype "passive"))
    )
    (net (code "60") (name "unconnected-(U5-UART_TX-Pad30)") (class "Default")
      (node (ref "U5") (pin "30") (pinfunction "UART_TX_30") (pintype "passive"))
    )
    (net (code "61") (name "unconnected-(U5-VBAT-Pad1)") (class "Default")
      (node (ref "U5") (pin "1") (pinfunction "VBAT_1") (pintype "passive"))
    )
    (net (code "62") (name "unconnected-(U6-NC-Pad7)") (class "Default")
      (node (ref "U6") (pin "7") (pinfunction "NC_7") (pintype "passive"))
    )
    (net (code "63") (name "unconnected-(U6-~{ALERT}-Pad6)") (class "Default")
      (node (ref "U6") (pin "6") (pinfunction "~{ALERT}_6") (pintype "passive"))
    )
    (net (code "64") (name "unconnected-(U7-CLK-Pad20)") (class "Default")
      (node (ref "U7") (pin "20") (pinfunction "CLK_20") (pintype "passive"))
    )
    (net (code "65") (name "unconnected-(U7-CMD-Pad19)") (class "Default")
      (node (ref "U7") (pin "19") (pinfunction "CMD_19") (pintype "passive"))
    )
    (net (code "66") (name "unconnected-(U7-IO0-Pad25)") (class "Default")
      (node (ref "U7") (pin "25") (pinfunction "IO0_25") (pintype "passive"))
    )
    (net (code "67") (name "unconnected-(U7-IO2-Pad24)") (class "Default")
      (node (ref "U7") (pin "24") (pinfunction "IO2_24") (pintype "passive"))
    )
    (net (code "68") (name "unconnected-(U7-IO4-Pad26)") (class "Default")
      (node (ref "U7") (pin "26") (pinfunction "IO4_26") (pintype "passive"))
    )
    (net (code "69") (name "unconnected-(U7-IO5-Pad29)") (class "Default")
      (node (ref "U7") (pin "29") (pinfunction "IO5_29") (pintype "passive"))
    )
    (net (code "70") (name "unconnected-(U7-IO12-Pad14)") (class "Default")
      (node (ref "U7") (pin "14") (pinfunction "IO12_14") (pintype "passive"))
    )
    (net (code "71") (name "unconnected-(U7-IO13-Pad16)") (class "Default")
      (node (ref "U7") (pin "16") (pinfunction "IO13_16") (pintype "passive"))
    )
    (net (code "72") (name "unconnected-(U7-IO14-Pad13)") (class "Default")
      (node (ref "U7") (pin "13") (pinfunction "IO14_13") (pintype "passive"))
    )
    (net (code "73") (name "unconnected-(U7-IO15-Pad23)") (class "Default")
      (node (ref "U7") (pin "23") (pinfunction "IO15_23") (pintype "passive"))
    )
    (net (code "74") (name "unconnected-(U7-IO16-Pad27)") (class "Default")
      (node (ref "U7") (pin "27") (pinfunction "IO16_27") (pintype "passive"))
    )
    (net (code "75") (name "unconnected-(U7-IO17-Pad28)") (class "Default")
      (node (ref "U7") (pin "28") (pinfunction "IO17_28") (pintype "passive"))
    )
    (net (code "76") (name "unconnected-(U7-IO18-Pad30)") (class "Default")
      (node (ref "U7") (pin "30") (pinfunction "IO18_30") (pintype "passive"))
    )
    (net (code "77") (name "unconnected-(U7-IO19-Pad31)") (class "Default")
      (node (ref "U7") (pin "31") (pinfunction "IO19_31") (pintype "passive"))
    )
    (net (code "78") (name "unconnected-(U7-IO21-Pad33)") (class "Default")
      (node (ref "U7") (pin "33") (pinfunction "IO21_33") (pintype "passive"))
    )
    (net (code "79") (name "unconnected-(U7-IO22-Pad36)") (class "Default")
      (node (ref "U7") (pin "36") (pinfunction "IO22_36") (pintype "passive"))
    )
    (net (code "80") (name "unconnected-(U7-IO23-Pad37)") (class "Default")
      (node (ref "U7") (pin "37") (pinfunction "IO23_37") (pintype "passive"))
    )
    (net (code "81") (name "unconnected-(U7-IO25-Pad10)") (class "Default")
      (node (ref "U7") (pin "10") (pinfunction "IO25_10") (pintype "passive"))
    )
    (net (code "82") (name "unconnected-(U7-IO26-Pad11)") (class "Default")
      (node (ref "U7") (pin "11") (pinfunction "IO26_11") (pintype "passive"))
    )
    (net (code "83") (name "unconnected-(U7-IO27-Pad12)") (class "Default")
      (node (ref "U7") (pin "12") (pinfunction "IO27_12") (pintype "passive"))
    )
    (net (code "84") (name "unconnected-(U7-IO32-Pad8)") (class "Default")
      (node (ref "U7") (pin "8") (pinfunction "IO32_8") (pintype "passive"))
    )
    (net (code "85") (name "unconnected-(U7-IO33-Pad9)") (class "Default")
      (node (ref "U7") (pin "9") (pinfunction "IO33_9") (pintype "passive"))
    )
    (net (code "86") (name "unconnected-(U7-IO34-Pad6)") (class "Default")
      (node (ref "U7") (pin "6") (pinfunction "IO34_6") (pintype "passive"))
    )
    (net (code "87") (name "unconnected-(U7-IO35-Pad7)") (class "Default")
      (node (ref "U7") (pin "7") (pinfunction "IO35_7") (pintype "passive"))
    )
    (net (code "88") (name "unconnected-(U7-NC-Pad32)") (class "Default")
      (node (ref "U7") (pin "32") (pinfunction "NC_32") (pintype "passive"))
    )
    (net (code "89") (name "unconnected-(U7-SD0-Pad21)") (class "Default")
      (node (ref "U7") (pin "21") (pinfunction "SD0_21") (pintype "passive"))
    )
    (net (code "90") (name "unconnected-(U7-SD1-Pad22)") (class "Default")
      (node (ref "U7") (pin "22") (pinfunction "SD1_22") (pintype "passive"))
    )
    (net (code "91") (name "unconnected-(U7-SD2-Pad17)") (class "Default")
      (node (ref "U7") (pin "17") (pinfunction "SD2_17") (pintype "passive"))
    )
    (net (code "92") (name "unconnected-(U7-SD3-Pad18)") (class "Default")
      (node (ref "U7") (pin "18") (pinfunction "SD3_18") (pintype "passive"))
    )
    (net (code "93") (name "unconnected-(U7-SENSOR_VN-Pad5)") (class "Default")
      (node (ref "U7") (pin "5") (pinfunction "SENSOR_VN_5") (pintype "passive"))
    )
    (net (code "94") (name "unconnected-(U7-SENSOR_VP-Pad4)") (class "Default")
      (node (ref "U7") (pin "4") (pinfunction "SENSOR_VP_4") (pintype "passive"))
    )
  )
)
